# Industrial-Controller_5V_Domain.net
KiCad netlist of a schematic drawn in Altium Designer
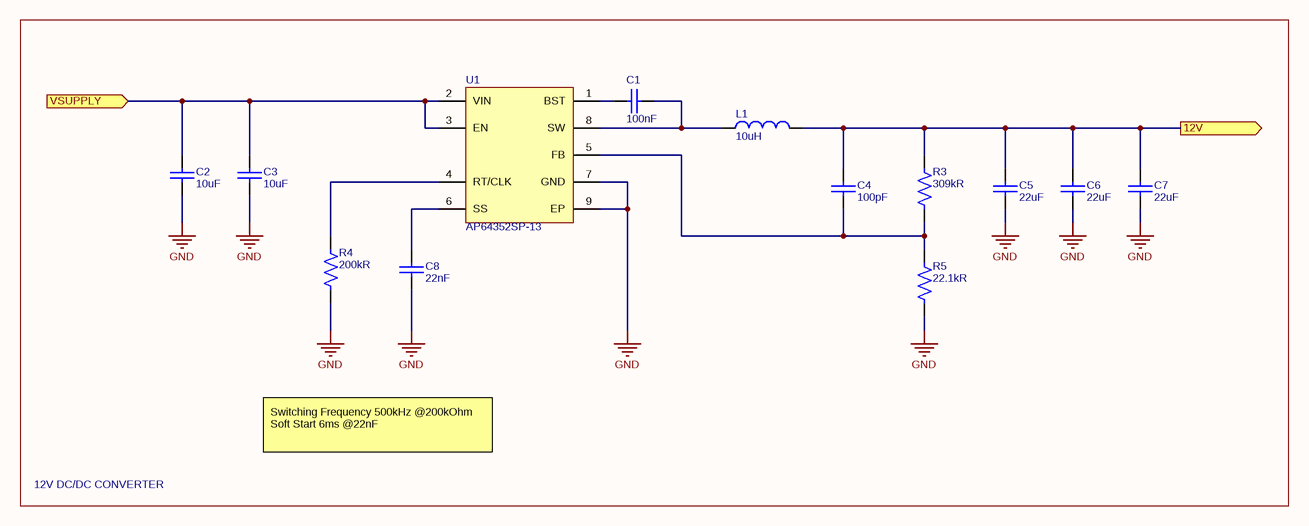
[diagram p0: Industrial-Controller_5V_Domain.SchDoc]

(export (version "E")
  (design (tool "Eeschema 10.0.6"))
  (components
    (comp (ref "C1")
      (value "100nF")
      (footprint "CAP_0603")
      (description "CAP CER 0.1UF 50V X7R 0603")
      (fields (field (name "TOLERANCE") "10%"))
      (libsource (lib "Door_Controller_Single") (part "CL10B104KB8NNNL"))
    )
    (comp (ref "C2")
      (value "10uF")
      (footprint "CAP_1210")
      (description "CAP CER 10UF 50V X7R 1210")
      (fields (field (name "TOLERANCE") "10%"))
      (libsource (lib "Door_Controller_Single") (part "CL32B106KBJNNWE"))
    )
    (comp (ref "C3")
      (value "10uF")
      (footprint "CAP_1210")
      (description "CAP CER 10UF 50V X7R 1210")
      (fields (field (name "TOLERANCE") "10%"))
      (libsource (lib "Door_Controller_Single") (part "CL32B106KBJNNWE"))
    )
    (comp (ref "C4")
      (value "100pF")
      (footprint "CAP_0603")
      (description "CAP CER 100PF 50V X7R 0603")
      (fields (field (name "TOLERANCE") "10%"))
      (libsource (lib "Door_Controller_Single") (part "CL10B101KB8NFNC"))
    )
    (comp (ref "C5")
      (value "22uF")
      (footprint "CAP_1210")
      (description "CAP CER 22UF 25V X7R 1210")
      (fields (field (name "TOLERANCE") "10%"))
      (libsource (lib "Door_Controller_Single") (part "CL32B226KAJNNNE"))
    )
    (comp (ref "C6")
      (value "22uF")
      (footprint "CAP_1210")
      (description "CAP CER 22UF 25V X7R 1210")
      (fields (field (name "TOLERANCE") "10%"))
      (libsource (lib "Door_Controller_Single") (part "CL32B226KAJNNNE"))
    )
    (comp (ref "C7")
      (value "22uF")
      (footprint "CAP_1210")
      (description "CAP CER 22UF 25V X7R 1210")
      (fields (field (name "TOLERANCE") "10%"))
      (libsource (lib "Door_Controller_Single") (part "CL32B226KAJNNNE"))
    )
    (comp (ref "C8")
      (value "22nF")
      (footprint "CAP_0603")
      (description "CAP CER 0.022UF 50V X7R 0603")
      (fields (field (name "TOLERANCE") "10%"))
      (libsource (lib "Door_Controller_Single") (part "CL10B223KB8WPNC"))
    )
    (comp (ref "L1")
      (value "10uH")
      (footprint "SRU1048")
      (description "FIXED IND 10UH 4.5A 18.5MOHM SMD")
      (fields (field (name "TOLERANCE") "30%"))
      (libsource (lib "Door_Controller_Single") (part "SRU1048-100Y"))
    )
    (comp (ref "R3")
      (value "309kR")
      (footprint "RES_0603")
      (description "RES 309K OHM 1% 1/10W 0603")
      (fields (field (name "TOLERANCE") "1%"))
      (libsource (lib "Door_Controller_Single") (part "RC0603FR-07309KL"))
    )
    (comp (ref "R4")
      (value "200kR")
      (footprint "RES_0603")
      (description "RES 200K OHM 1% 1/10W 0603")
      (fields (field (name "TOLERANCE") "1%"))
      (libsource (lib "Door_Controller_Single") (part "RC0603FR-07200KL"))
    )
    (comp (ref "R5")
      (value "22.1kR")
      (footprint "RES_0603")
      (description "RES 22.1K OHM 1% 1/10W 0603")
      (fields (field (name "TOLERANCE") "1%"))
      (libsource (lib "Door_Controller_Single") (part "RC0603FR-0722K1L"))
    )
    (comp (ref "U1")
      (value "AP64352SP-13")
      (footprint "SOIC-8EP_150mil")
      (description "IC DCDC CONV BUCK 3.5A SO-8EP")
      (libsource (lib "Door_Controller_Single") (part "AP64352SP-13"))
    )
  )
  (nets
    (net (code "1") (name "/12V") (class "Default")
      (node (ref "C4") (pin "2") (pinfunction "2_2") (pintype "passive"))
      (node (ref "C5") (pin "2") (pinfunction "2_2") (pintype "passive"))
      (node (ref "C6") (pin "2") (pinfunction "2_2") (pintype "passive"))
      (node (ref "C7") (pin "2") (pinfunction "2_2") (pintype "passive"))
      (node (ref "L1") (pin "2") (pinfunction "2_2") (pintype "passive"))
      (node (ref "R3") (pin "1") (pinfunction "1_1") (pintype "passive"))
    )
    (net (code "2") (name "/VSUPPLY") (class "Default")
      (node (ref "C2") (pin "2") (pinfunction "2_2") (pintype "passive"))
      (node (ref "C3") (pin "2") (pinfunction "2_2") (pintype "passive"))
      (node (ref "U1") (pin "2") (pinfunction "VIN_2") (pintype "passive"))
      (node (ref "U1") (pin "3") (pinfunction "EN_3") (pintype "passive"))
    )
    (net (code "3") (name "GND") (class "Default")
      (node (ref "C2") (pin "1") (pinfunction "1_1") (pintype "passive"))
      (node (ref "C3") (pin "1") (pinfunction "1_1") (pintype "passive"))
      (node (ref "C5") (pin "1") (pinfunction "1_1") (pintype "passive"))
      (node (ref "C6") (pin "1") (pinfunction "1_1") (pintype "passive"))
      (node (ref "C7") (pin "1") (pinfunction "1_1") (pintype "passive"))
      (node (ref "C8") (pin "1") (pinfunction "1_1") (pintype "passive"))
      (node (ref "R4") (pin "2") (pinfunction "2_2") (pintype "passive"))
      (node (ref "R5") (pin "2") (pinfunction "2_2") (pintype "passive"))
      (node (ref "U1") (pin "7") (pinfunction "GND_7") (pintype "passive"))
      (node (ref "U1") (pin "9") (pinfunction "EP_9") (pintype "passive"))
    )
    (net (code "4") (name "Net-(U1-BST)") (class "Default")
      (node (ref "C1") (pin "2") (pinfunction "2_2") (pintype "passive"))
      (node (ref "U1") (pin "1") (pinfunction "BST_1") (pintype "passive"))
    )
    (net (code "5") (name "Net-(U1-FB)") (class "Default")
      (node (ref "C4") (pin "1") (pinfunction "1_1") (pintype "passive"))
      (node (ref "R3") (pin "2") (pinfunction "2_2") (pintype "passive"))
      (node (ref "R5") (pin "1") (pinfunction "1_1") (pintype "passive"))
      (node (ref "U1") (pin "5") (pinfunction "FB_5") (pintype "passive"))
    )
    (net (code "6") (name "Net-(U1-RT{slash}CLK)") (class "Default")
      (node (ref "R4") (pin "1") (pinfunction "1_1") (pintype "passive"))
      (node (ref "U1") (pin "4") (pinfunction "RT/CLK_4") (pintype "passive"))
    )
    (net (code "7") (name "Net-(U1-SS)") (class "Default")
      (node (ref "C8") (pin "2") (pinfunction "2_2") (pintype "passive"))
      (node (ref "U1") (pin "6") (pinfunction "SS_6") (pintype "passive"))
    )
    (net (code "8") (name "Net-(U1-SW)") (class "Default")
      (node (ref "C1") (pin "1") (pinfunction "1_1") (pintype "passive"))
      (node (ref "L1") (pin "1") (pinfunction "1_1") (pintype "passive"))
      (node (ref "U1") (pin "8") (pinfunction "SW_8") (pintype "passive"))
    )
  )
)
